# Battery-Cutoff.net
KiCad netlist of a schematic drawn in Altium Designer
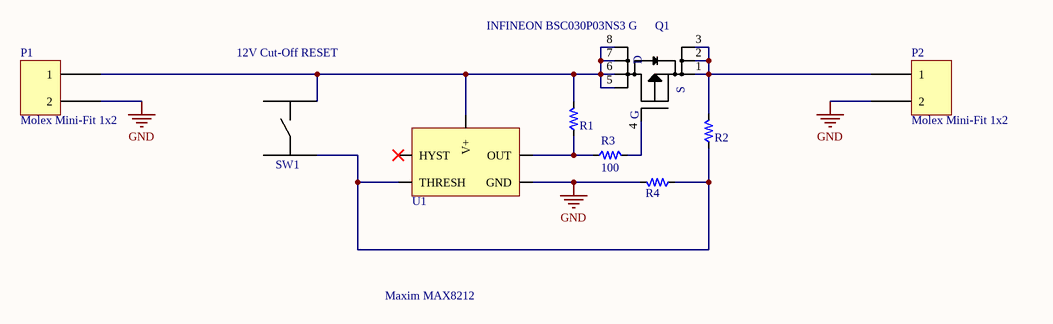
[diagram p0: Battery-Cutoff.SchDoc]

(export (version "E")
  (design (tool "Eeschema 10.0.6"))
  (components
    (comp (ref "P1")
      (value "Molex Mini-Fit 1x2")
      (footprint "Molex Mini-Fit Jr 2x1")
      (libsource (lib "") (part "Molex Mini-Fit 1x2_1"))
    )
    (comp (ref "P2")
      (value "Molex Mini-Fit 1x2")
      (footprint "Molex Mini-Fit Jr 2x1")
      (libsource (lib "Molex Mini-Fit Jr 1x2") (part "Molex Mini-Fit 1x2"))
    )
    (comp (ref "Q1")
      (value "INFINEON BSC030P03NS3 G")
      (footprint "BSC030P03NS3 G")
      (description "P-Channel 30V 25.4A (Ta), 100A (Tc) 2.5W (Ta), 125W (Tc) Surface Mount PG-TDSON-8")
      (fields (field (name "DIGIKEY PART NO.") "BSC030P03NS3 GCT-ND"))
      (libsource (lib "Infineon BSC030P03NS3 G - 8-PowerTDFN - PMOS") (part "BSC030P03NS3 G"))
    )
    (comp (ref "R1")
      (value "SCH_GENERIC_RESISTOR_0603")
      (footprint "PCB_GENERIC_SMD_0603")
      (description "Generic SMD resistor 0603")
      (libsource (lib "Generic 0603 Resistor") (part "SCH_GENERIC_RESISTOR_0603"))
    )
    (comp (ref "R2")
      (value "SCH_GENERIC_RESISTOR_0603")
      (footprint "PCB_GENERIC_SMD_0603")
      (description "Generic SMD resistor 0603")
      (libsource (lib "Generic 0603 Resistor") (part "SCH_GENERIC_RESISTOR_0603"))
    )
    (comp (ref "R3")
      (value "SCH_GENERIC_RESISTOR_0603")
      (footprint "PCB_GENERIC_SMD_0603")
      (description "Generic SMD resistor 0603")
      (fields (field (name "RESISTANCE") "100"))
      (libsource (lib "Generic 0603 Resistor") (part "SCH_GENERIC_RESISTOR_0603"))
    )
    (comp (ref "R4")
      (value "SCH_GENERIC_RESISTOR_0603")
      (footprint "PCB_GENERIC_SMD_0603")
      (description "Generic SMD resistor 0603")
      (libsource (lib "Generic 0603 Resistor") (part "SCH_GENERIC_RESISTOR_0603"))
    )
    (comp (ref "SW1")
      (value "Tactile Switch")
      (footprint "C&K 4 pin Tactile Switch")
      (libsource (lib "C&K 4 Pin Tactile Switch") (part "C&K Tactile Switch"))
    )
    (comp (ref "U1")
      (value "Maxim MAX8212")
      (footprint "Maxim MAX8212")
      (libsource (lib "Maxim MAX8212") (part "Maxim MAX8212"))
    )
  )
  (nets
    (net (code "1") (name "GND") (class "Default")
      (node (ref "P1") (pin "2") (pinfunction "2_2") (pintype "passive"))
      (node (ref "P2") (pin "2") (pinfunction "2_2") (pintype "passive"))
      (node (ref "R4") (pin "2") (pinfunction "2_2") (pintype "passive"))
      (node (ref "U1") (pin "5") (pinfunction "GND_5") (pintype "passive"))
    )
    (net (code "2") (name "Net-(P2-Pad1)") (class "Default")
      (node (ref "P2") (pin "1") (pinfunction "1_1") (pintype "passive"))
      (node (ref "Q1") (pin "1") (pinfunction "S_1") (pintype "passive"))
      (node (ref "Q1") (pin "2") (pinfunction "S_2") (pintype "passive"))
      (node (ref "Q1") (pin "3") (pinfunction "S_3") (pintype "passive"))
      (node (ref "R2") (pin "2") (pinfunction "2_2") (pintype "passive"))
    )
    (net (code "3") (name "Net-(Q1-G)") (class "Default")
      (node (ref "Q1") (pin "4") (pinfunction "G_4") (pintype "passive"))
      (node (ref "R3") (pin "2") (pinfunction "2_2") (pintype "passive"))
    )
    (net (code "4") (name "Net-(U1-OUT)") (class "Default")
      (node (ref "R1") (pin "1") (pinfunction "1_1") (pintype "passive"))
      (node (ref "R3") (pin "1") (pinfunction "1_1") (pintype "passive"))
      (node (ref "U1") (pin "4") (pinfunction "OUT_4") (pintype "passive"))
    )
    (net (code "5") (name "Net-(U1-THRESH)") (class "Default")
      (node (ref "R2") (pin "1") (pinfunction "1_1") (pintype "passive"))
      (node (ref "R4") (pin "1") (pinfunction "1_1") (pintype "passive"))
      (node (ref "SW1") (pin "1") (pintype "passive"))
      (node (ref "U1") (pin "3") (pinfunction "THRESH_3") (pintype "passive"))
    )
    (net (code "6") (name "Net-(U1-V+)") (class "Default")
      (node (ref "P1") (pin "1") (pinfunction "1_1") (pintype "passive"))
      (node (ref "Q1") (pin "5") (pinfunction "D_5") (pintype "passive"))
      (node (ref "Q1") (pin "6") (pinfunction "D_6") (pintype "passive"))
      (node (ref "Q1") (pin "7") (pinfunction "D_7") (pintype "passive"))
      (node (ref "Q1") (pin "8") (pinfunction "D_8") (pintype "passive"))
      (node (ref "R1") (pin "2") (pinfunction "2_2") (pintype "passive"))
      (node (ref "SW1") (pin "3") (pinfunction "3_3") (pintype "passive"))
      (node (ref "U1") (pin "8") (pinfunction "V+_8") (pintype "passive"))
    )
    (net (code "7") (name "unconnected-(SW1-Pad2)") (class "Default")
      (node (ref "SW1") (pin "2") (pinfunction "2_2") (pintype "passive"))
    )
    (net (code "8") (name "unconnected-(SW1-Pad4)") (class "Default")
      (node (ref "SW1") (pin "4") (pinfunction "4_4") (pintype "passive"))
    )
    (net (code "9") (name "unconnected-(U1-HYST-Pad2)") (class "Default")
      (node (ref "U1") (pin "2") (pinfunction "HYST_2") (pintype "passive+no_connect"))
    )
  )
)
